# Trinamic.net
KiCad netlist of a schematic drawn in Altium Designer
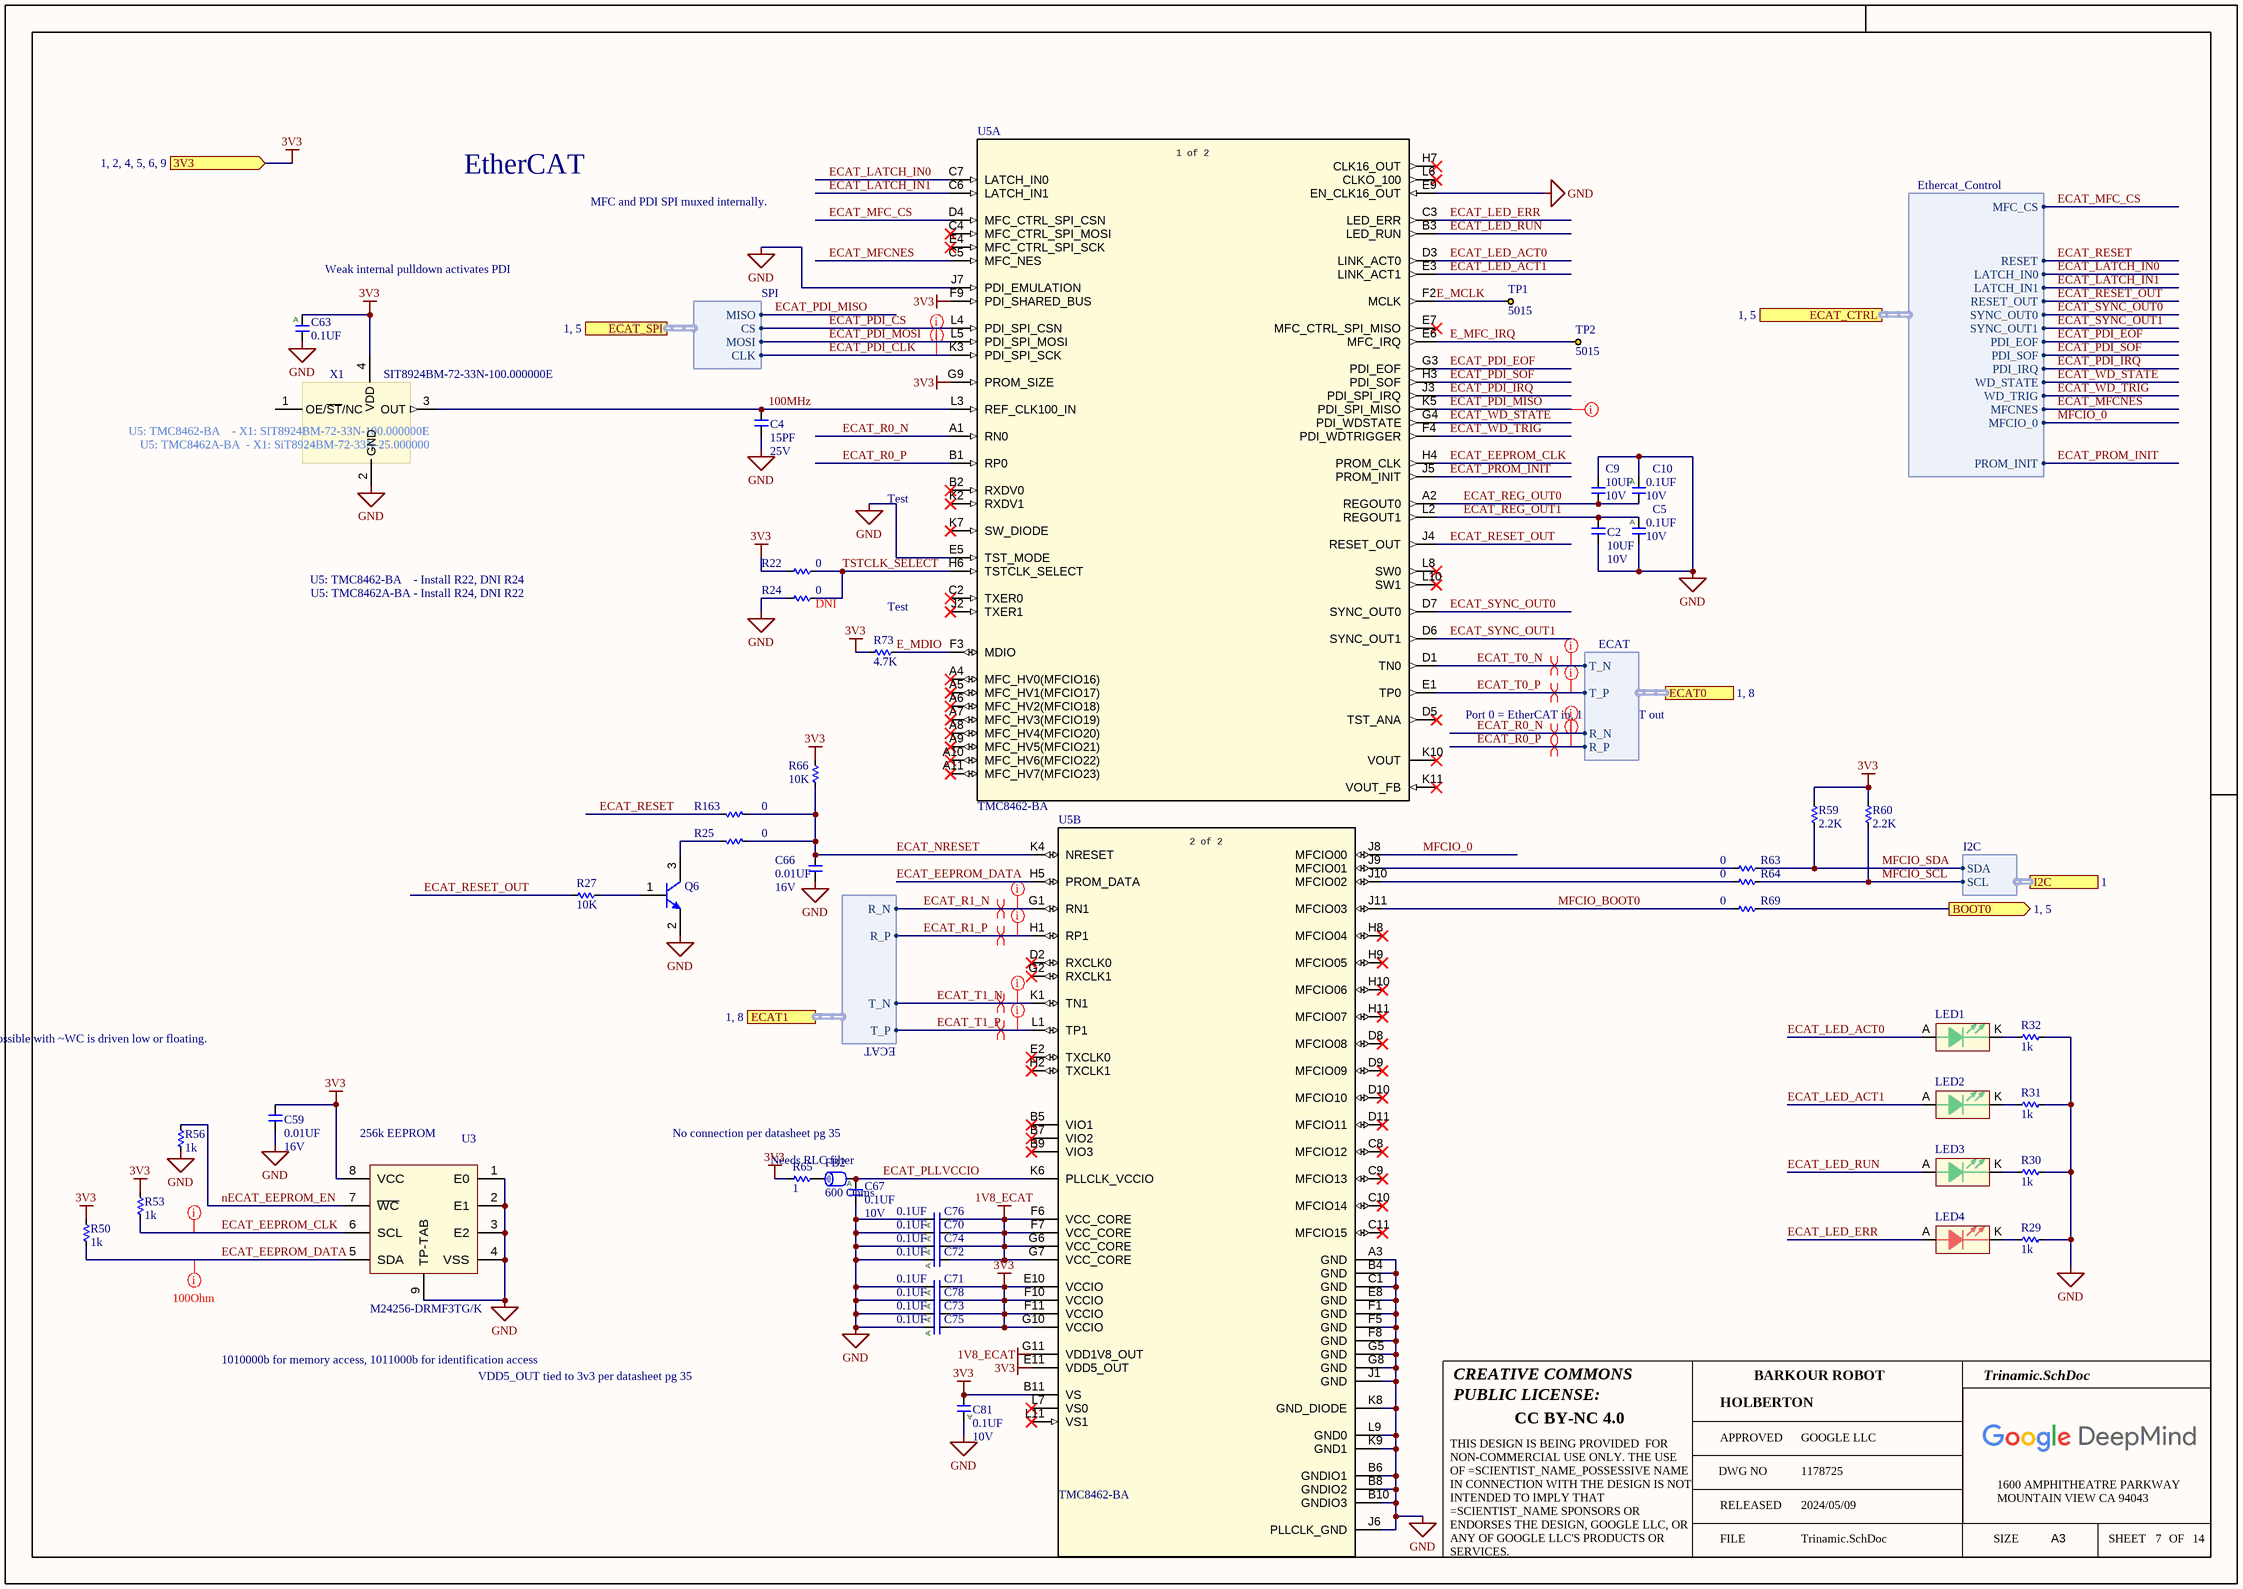
[diagram p0: Trinamic.SchDoc]

(export (version "E")
  (design (tool "Eeschema 10.0.6"))
  (components
    (comp (ref "C2")
      (value "10UF")
      (footprint "C0402")
      (description "CAP, CER, X5R, 10uF, 10V, 20%, 0402, 0.7mm T")
      (fields
        (field (name "MFG") "SAMSUNG")
        (field (name "VOLTAGE") "10V")
        (field (name "Comment") "__Template_Cap")
      )
      (libsource (lib "AltiumReleaseLibDB") (part "__Template_Cap"))
    )
    (comp (ref "C4")
      (value "15PF")
      (footprint "C0201")
      (description "CAP, CER, NP0, 15pF, 25V, 5%, 0201, 0.9mm T")
      (fields
        (field (name "MFG") "TDK")
        (field (name "VOLTAGE") "25V")
        (field (name "Comment") "__Template_Cap")
      )
      (libsource (lib "AltiumReleaseLibDB") (part "__Template_Cap"))
    )
    (comp (ref "C5")
      (value "0.1UF")
      (footprint "C0201")
      (description "CAP, CER, X6S, 0.1uF, 10V, 10%, 0201, AUTOGRADE")
      (fields
        (field (name "MFG") "MURATA")
        (field (name "VOLTAGE") "10V")
        (field (name "Comment") "__Template_Cap_Auto")
      )
      (libsource (lib "AltiumReleaseLibDB") (part "__Template_Cap_Auto"))
    )
    (comp (ref "C9")
      (value "10UF")
      (footprint "C0402")
      (description "CAP, CER, X5R, 10uF, 10V, 20%, 0402, 0.7mm T")
      (fields
        (field (name "MFG") "SAMSUNG")
        (field (name "VOLTAGE") "10V")
        (field (name "Comment") "__Template_Cap")
      )
      (libsource (lib "AltiumReleaseLibDB") (part "__Template_Cap"))
    )
    (comp (ref "C10")
      (value "0.1UF")
      (footprint "C0201")
      (description "CAP, CER, X6S, 0.1uF, 10V, 10%, 0201, AUTOGRADE")
      (fields
        (field (name "MFG") "MURATA")
        (field (name "VOLTAGE") "10V")
        (field (name "Comment") "__Template_Cap_Auto")
      )
      (libsource (lib "AltiumReleaseLibDB") (part "__Template_Cap_Auto"))
    )
    (comp (ref "C59")
      (value "0.01UF")
      (footprint "C0201")
      (description "CAP, CER, X5R, 0.01uF, 16V, 10%, 0201, 0.33mm T")
      (fields
        (field (name "MFG") "MURATA")
        (field (name "VOLTAGE") "16V")
        (field (name "Comment") "__Template_Cap")
      )
      (libsource (lib "AltiumReleaseLibDB") (part "__Template_Cap"))
    )
    (comp (ref "C63")
      (value "0.1UF")
      (footprint "C0201")
      (description "CAP, CER, X6S, 0.1uF, 10V, 10%, 0201, AUTOGRADE")
      (fields (field (name "MFG") "MURATA") (field (name "VOLTAGE") "10V"))
      (libsource (lib "AltiumReleaseLibDB") (part "__Template_Cap_Auto"))
    )
    (comp (ref "C66")
      (value "0.01UF")
      (footprint "C0201")
      (description "CAP, CER, X5R, 0.01uF, 16V, 10%, 0201, 0.33mm T")
      (fields
        (field (name "MFG") "MURATA")
        (field (name "VOLTAGE") "16V")
        (field (name "Comment") "__Template_Cap")
      )
      (libsource (lib "AltiumReleaseLibDB") (part "__Template_Cap"))
    )
    (comp (ref "C67")
      (value "0.1UF")
      (footprint "C0201")
      (description "CAP, CER, X6S, 0.1uF, 10V, 10%, 0201, AUTOGRADE")
      (fields
        (field (name "MFG") "MURATA")
        (field (name "VOLTAGE") "10V")
        (field (name "Comment") "__Template_Cap_Auto")
      )
      (libsource (lib "AltiumReleaseLibDB") (part "__Template_Cap_Auto"))
    )
    (comp (ref "C70")
      (value "0.1UF")
      (footprint "C0201")
      (description "CAP, CER, X6S, 0.1uF, 10V, 10%, 0201, AUTOGRADE")
      (fields (field (name "MFG") "MURATA") (field (name "VOLTAGE") "10V"))
      (libsource (lib "AltiumReleaseLibDB") (part "__Template_Cap_Auto"))
    )
    (comp (ref "C71")
      (value "0.1UF")
      (footprint "C0201")
      (description "CAP, CER, X6S, 0.1uF, 10V, 10%, 0201, AUTOGRADE")
      (fields (field (name "MFG") "MURATA") (field (name "VOLTAGE") "10V"))
      (libsource (lib "AltiumReleaseLibDB") (part "__Template_Cap_Auto"))
    )
    (comp (ref "C72")
      (value "0.1UF")
      (footprint "C0201")
      (description "CAP, CER, X6S, 0.1uF, 10V, 10%, 0201, AUTOGRADE")
      (fields (field (name "MFG") "MURATA") (field (name "VOLTAGE") "10V"))
      (libsource (lib "AltiumReleaseLibDB") (part "__Template_Cap_Auto"))
    )
    (comp (ref "C73")
      (value "0.1UF")
      (footprint "C0201")
      (description "CAP, CER, X6S, 0.1uF, 10V, 10%, 0201, AUTOGRADE")
      (fields (field (name "MFG") "MURATA") (field (name "VOLTAGE") "10V"))
      (libsource (lib "AltiumReleaseLibDB") (part "__Template_Cap_Auto"))
    )
    (comp (ref "C74")
      (value "0.1UF")
      (footprint "C0201")
      (description "CAP, CER, X6S, 0.1uF, 10V, 10%, 0201, AUTOGRADE")
      (fields (field (name "MFG") "MURATA") (field (name "VOLTAGE") "10V"))
      (libsource (lib "AltiumReleaseLibDB") (part "__Template_Cap_Auto"))
    )
    (comp (ref "C75")
      (value "0.1UF")
      (footprint "C0201")
      (description "CAP, CER, X6S, 0.1uF, 10V, 10%, 0201, AUTOGRADE")
      (fields (field (name "MFG") "MURATA") (field (name "VOLTAGE") "10V"))
      (libsource (lib "AltiumReleaseLibDB") (part "__Template_Cap_Auto"))
    )
    (comp (ref "C76")
      (value "0.1UF")
      (footprint "C0201")
      (description "CAP, CER, X6S, 0.1uF, 10V, 10%, 0201, AUTOGRADE")
      (fields (field (name "MFG") "MURATA") (field (name "VOLTAGE") "10V"))
      (libsource (lib "AltiumReleaseLibDB") (part "__Template_Cap_Auto"))
    )
    (comp (ref "C78")
      (value "0.1UF")
      (footprint "C0201")
      (description "CAP, CER, X6S, 0.1uF, 10V, 10%, 0201, AUTOGRADE")
      (fields (field (name "MFG") "MURATA") (field (name "VOLTAGE") "10V"))
      (libsource (lib "AltiumReleaseLibDB") (part "__Template_Cap_Auto"))
    )
    (comp (ref "C81")
      (value "0.1UF")
      (footprint "C0201")
      (description "CAP, CER, X6S, 0.1uF, 10V, 10%, 0201, AUTOGRADE")
      (fields
        (field (name "MFG") "MURATA")
        (field (name "VOLTAGE") "10V")
        (field (name "Comment") "__Template_Cap_Auto")
      )
      (libsource (lib "AltiumReleaseLibDB") (part "__Template_Cap_Auto"))
    )
    (comp (ref "FB2")
      (value "600 Ohms")
      (footprint "L0201_H0.33MM")
      (description "FERRITE, BEAD, 600OHMS @100MHZ, 25%, 250mA, 900 mOHM DCR, 0201")
      (fields
        (field (name "MFG") "Murata Electronics North America")
        (field (name "Comment") "__Template_Ferrite_Bead")
      )
      (libsource (lib "AltiumReleaseLibDB") (part "__Template_Ferrite_Bead"))
    )
    (comp (ref "LED1")
      (value "__Template_LED_GREEN_AK")
      (footprint "LED_APHHS1005LCGCK")
      (description "LED, GREEN, 574nm, 2mA, CLEAR, 0402")
      (fields (field (name "MFG") "Kingbright"))
      (libsource (lib "AltiumReleaseLibDB") (part "__Template_LED_GREEN_AK"))
    )
    (comp (ref "LED2")
      (value "__Template_LED_GREEN_AK")
      (footprint "LED_APHHS1005LCGCK")
      (description "LED, GREEN, 574nm, 2mA, CLEAR, 0402")
      (fields (field (name "MFG") "Kingbright"))
      (libsource (lib "AltiumReleaseLibDB") (part "__Template_LED_GREEN_AK"))
    )
    (comp (ref "LED3")
      (value "__Template_LED_GREEN_AK")
      (footprint "LED_APHHS1005LCGCK")
      (description "LED, GREEN, 574nm, 2mA, CLEAR, 0402")
      (fields (field (name "MFG") "Kingbright"))
      (libsource (lib "AltiumReleaseLibDB") (part "__Template_LED_GREEN_AK"))
    )
    (comp (ref "LED4")
      (value "__Template_LED_RED_AK")
      (footprint "LED_APHHS1005LCGCK")
      (description "LED, RED, 640NM, 2mA, CLEAR, 0402")
      (fields (field (name "MFG") "Kingbright"))
      (libsource (lib "AltiumReleaseLibDB") (part "__Template_LED_RED_AK"))
    )
    (comp (ref "Q6")
      (value "Bipolar NPN 3 Pins Transistor Gummel-Poon Model")
      (footprint "SOT23-3")
      (description "TRANS NPN 40V 0.2A SOT23-3")
      (fields (field (name "MFG") "NTE Electronics, Inc"))
      (libsource (lib "Holberton_V1") (part "BJT NPN_GP"))
    )
    (comp (ref "R22")
      (value "0")
      (footprint "R0402")
      (description "RES, 0, JUMPER, 1/16W, 0402")
      (fields (field (name "MFG") "YAGEO"))
      (libsource (lib "AltiumReleaseLibDB") (part "__Template_Resistor"))
    )
    (comp (ref "R24")
      (value "0")
      (footprint "R0402")
      (description "RES, 0, JUMPER, 1/16W, 0402")
      (fields (field (name "MFG") "YAGEO") (field (name "DNI") "DNI"))
      (libsource (lib "AltiumReleaseLibDB") (part "__Template_Resistor"))
    )
    (comp (ref "R25")
      (value "0")
      (footprint "R0402")
      (description "RES, 0, JUMPER, 1/16W, 0402")
      (fields (field (name "MFG") "YAGEO"))
      (libsource (lib "AltiumReleaseLibDB") (part "__Template_Resistor"))
    )
    (comp (ref "R27")
      (value "10K")
      (footprint "R0201")
      (description "RES, 10K, 1%, 1/20W, 0201, AUTOGRADE")
      (fields (field (name "MFG") "PANASONIC") (field (name "Comment") "__Template_Resistor"))
      (libsource (lib "AltiumReleaseLibDB") (part "__Template_Resistor"))
    )
    (comp (ref "R29")
      (value "1k")
      (footprint "R0201")
      (description "RES, 1K, 1%, 1/20W, 0201, AUTOGRADE")
      (fields (field (name "MFG") "Bourns Inc.") (field (name "Comment") "__Template_Resistor"))
      (libsource (lib "AltiumReleaseLibDB") (part "__Template_Resistor"))
    )
    (comp (ref "R30")
      (value "1k")
      (footprint "R0201")
      (description "RES, 1K, 1%, 1/20W, 0201, AUTOGRADE")
      (fields (field (name "MFG") "Bourns Inc.") (field (name "Comment") "__Template_Resistor"))
      (libsource (lib "AltiumReleaseLibDB") (part "__Template_Resistor"))
    )
    (comp (ref "R31")
      (value "1k")
      (footprint "R0201")
      (description "RES, 1K, 1%, 1/20W, 0201, AUTOGRADE")
      (fields (field (name "MFG") "Bourns Inc.") (field (name "Comment") "__Template_Resistor"))
      (libsource (lib "AltiumReleaseLibDB") (part "__Template_Resistor"))
    )
    (comp (ref "R32")
      (value "1k")
      (footprint "R0201")
      (description "RES, 1K, 1%, 1/20W, 0201, AUTOGRADE")
      (fields (field (name "MFG") "Bourns Inc.") (field (name "Comment") "__Template_Resistor"))
      (libsource (lib "AltiumReleaseLibDB") (part "__Template_Resistor"))
    )
    (comp (ref "R50")
      (value "1k")
      (footprint "R0201")
      (description "RES, 1K, 1%, 1/20W, 0201, AUTOGRADE")
      (fields (field (name "MFG") "Bourns Inc.") (field (name "Comment") "__Template_Resistor"))
      (libsource (lib "AltiumReleaseLibDB") (part "__Template_Resistor"))
    )
    (comp (ref "R53")
      (value "1k")
      (footprint "R0201")
      (description "RES, 1K, 1%, 1/20W, 0201, AUTOGRADE")
      (fields (field (name "MFG") "Bourns Inc.") (field (name "Comment") "__Template_Resistor"))
      (libsource (lib "AltiumReleaseLibDB") (part "__Template_Resistor"))
    )
    (comp (ref "R56")
      (value "1k")
      (footprint "R0201")
      (description "RES, 1K, 1%, 1/20W, 0201, AUTOGRADE")
      (fields (field (name "MFG") "Bourns Inc.") (field (name "Comment") "__Template_Resistor"))
      (libsource (lib "AltiumReleaseLibDB") (part "__Template_Resistor"))
    )
    (comp (ref "R59")
      (value "2.2K")
      (footprint "R0201")
      (description "Resistor, 2.20K Ohms, 0201, 0.05W, ±1%")
      (fields (field (name "MFG") "PANASONIC"))
      (libsource (lib "AltiumReleaseLibDB") (part "__Template_Resistor"))
    )
    (comp (ref "R60")
      (value "2.2K")
      (footprint "R0201")
      (description "Resistor, 2.20K Ohms, 0201, 0.05W, ±1%")
      (fields (field (name "MFG") "PANASONIC"))
      (libsource (lib "AltiumReleaseLibDB") (part "__Template_Resistor"))
    )
    (comp (ref "R63")
      (value "0")
      (footprint "R0402")
      (description "RES, 0, JUMPER, 1/16W, 0402")
      (fields (field (name "MFG") "YAGEO"))
      (libsource (lib "AltiumReleaseLibDB") (part "__Template_Resistor"))
    )
    (comp (ref "R64")
      (value "0")
      (footprint "R0402")
      (description "RES, 0, JUMPER, 1/16W, 0402")
      (fields (field (name "MFG") "YAGEO"))
      (libsource (lib "AltiumReleaseLibDB") (part "__Template_Resistor"))
    )
    (comp (ref "R65")
      (value "1")
      (footprint "R0201")
      (description "RES, 1.0, 5%, 1/20W, 0201")
      (fields (field (name "MFG") "PANASONIC"))
      (libsource (lib "AltiumReleaseLibDB") (part "__Template_Resistor"))
    )
    (comp (ref "R66")
      (value "10K")
      (footprint "R0201")
      (description "RES, 10K, 1%, 1/20W, 0201, AUTOGRADE")
      (fields (field (name "MFG") "PANASONIC") (field (name "Comment") "__Template_Resistor"))
      (libsource (lib "AltiumReleaseLibDB") (part "__Template_Resistor"))
    )
    (comp (ref "R69")
      (value "0")
      (footprint "R0402")
      (description "RES, 0, JUMPER, 1/16W, 0402")
      (fields (field (name "MFG") "YAGEO"))
      (libsource (lib "AltiumReleaseLibDB") (part "__Template_Resistor"))
    )
    (comp (ref "R73")
      (value "4.7K")
      (footprint "R0201")
      (description "RES, 4.7K, 1%, 1/20W, 0201, AUTOGRADE")
      (fields
        (field (name "MFG") "Panasonic Electronic Components")
        (field (name "Comment") "__Template_Resistor")
      )
      (libsource (lib "AltiumReleaseLibDB") (part "__Template_Resistor"))
    )
    (comp (ref "R163")
      (value "0")
      (footprint "R0402")
      (description "RES, 0, JUMPER, 1/16W, 0402")
      (fields (field (name "MFG") "YAGEO"))
      (libsource (lib "AltiumReleaseLibDB") (part "__Template_Resistor"))
    )
    (comp (ref "TP1")
      (value "TP_KEYSTONE_5015")
      (footprint "TP_KEYSTONE_5015")
      (description "PC TEST POINT MINIATURE SMT")
      (fields (field (name "MFG") "Keystone Electronics") (field (name "MFG P/N") "5015"))
      (libsource (lib "AltiumReleaseLibDB") (part "TEST_KEYSTONE5015_NOSILK"))
    )
    (comp (ref "TP2")
      (value "TP_KEYSTONE_5015")
      (footprint "TP_KEYSTONE_5015")
      (description "PC TEST POINT MINIATURE SMT")
      (fields (field (name "MFG") "Keystone Electronics") (field (name "MFG P/N") "5015"))
      (libsource (lib "AltiumReleaseLibDB") (part "TEST_KEYSTONE5015_NOSILK"))
    )
    (comp (ref "U3")
      (value "EEPROM_M24256-DRMF3TG/K")
      (footprint "8WFDFN300X200X80-8-TP")
      (description "IC, MEMORY, M24256, EEPROM, 256Kb, I2C, 1MHz, MLP-8, AUTOGRADE")
      (fields (field (name "MFG") "STMicroelectronics") (field (name "MFG P/N") "M24256-DRMF3TG/K"))
      (libsource (lib "AltiumReleaseLibDB") (part "EEPROM_M24256-DRMF3TG/K"))
    )
    (comp (ref "U5")
      (value "PROCESSOR_TRINAMIC_TMC8462-BA")
      (footprint "BGA121C75P11X11_900X900X145")
      (description "IC, CONTROLLER, TMC8462, ETHERNET, 100Mb, SPI, PWM O/P, 100mA, BGA-121")
      (fields (field (name "MFG") "Trinamic Motion Control GmbH") (field (name "MFG P/N") "TMC8462-BA"))
      (libsource (lib "AltiumReleaseLibDB") (part "PROCESSOR_TRINAMIC_TMC8462-BA"))
    )
    (comp (ref "X1")
      (value "XTAL_SIT8924BM-72-33N-100.000000")
      (footprint "XTAL_SIT8924BM-72-33N-100.000000")
      (description "OSC, MEMS, XO, 100MHZ, +/-25PPM STAB, LVCMOS, 3.3V, SMD-4, AUTOGRADE")
      (fields (field (name "MFG") "SiTIME") (field (name "MFG P/N") "SIT8924BM-72-33N-100.000000E"))
      (libsource (lib "AltiumReleaseLibDB") (part "XTAL_SIT8924BM-72-33N-100.000000"))
    )
  )
  (nets
    (net (code "5") (name "/100MHz") (class "Default")
      (node (ref "C4") (pin "1") (pintype "passive"))
      (node (ref "U5") (pin "L3") (pinfunction "REF_CLK100_IN_L3") (pintype "input"))
      (node (ref "X1") (pin "3") (pinfunction "OUT_3") (pintype "output"))
    )
    (net (code "6") (name "/BOOT0") (class "Default") (node (ref "R69") (pin "2") (pintype "passive")))
    (net (code "7") (name "/ECAT_EEPROM_CLK") (class "Default")
      (node (ref "R53") (pin "1") (pintype "passive"))
      (node (ref "U3") (pin "6") (pinfunction "SCL_6") (pintype "passive"))
      (node (ref "U5") (pin "H4") (pinfunction "PROM_CLK_H4") (pintype "output"))
    )
    (net (code "8") (name "/ECAT_EEPROM_DATA") (class "Default")
      (node (ref "R50") (pin "1") (pintype "passive"))
      (node (ref "U3") (pin "5") (pinfunction "SDA_5") (pintype "passive"))
      (node (ref "U5") (pin "H5") (pinfunction "PROM_DATA_H5") (pintype "bidirectional"))
    )
    (net (code "9") (name "/ECAT_LATCH_IN0") (class "Default")
      (node (ref "U5") (pin "C7") (pinfunction "LATCH_IN0_C7") (pintype "input"))
    )
    (net (code "10") (name "/ECAT_LATCH_IN1") (class "Default")
      (node (ref "U5") (pin "C6") (pinfunction "LATCH_IN1_C6") (pintype "input"))
    )
    (net (code "11") (name "/ECAT_LED_ACT0") (class "Default")
      (node (ref "LED1") (pin "A") (pinfunction "A_A") (pintype "passive"))
      (node (ref "U5") (pin "D3") (pinfunction "LINK_ACT0_D3") (pintype "output"))
    )
    (net (code "12") (name "/ECAT_LED_ACT1") (class "Default")
      (node (ref "LED2") (pin "A") (pinfunction "A_A") (pintype "passive"))
      (node (ref "U5") (pin "E3") (pinfunction "LINK_ACT1_E3") (pintype "output"))
    )
    (net (code "13") (name "/ECAT_LED_ERR") (class "Default")
      (node (ref "LED4") (pin "A") (pinfunction "A_A") (pintype "passive"))
      (node (ref "U5") (pin "C3") (pinfunction "LED_ERR_C3") (pintype "output"))
    )
    (net (code "14") (name "/ECAT_LED_RUN") (class "Default")
      (node (ref "LED3") (pin "A") (pinfunction "A_A") (pintype "passive"))
      (node (ref "U5") (pin "B3") (pinfunction "LED_RUN_B3") (pintype "output"))
    )
    (net (code "15") (name "/ECAT_MFCNES") (class "Default")
      (node (ref "U5") (pin "C5") (pinfunction "MFC_NES_C5") (pintype "input"))
    )
    (net (code "16") (name "/ECAT_MFC_CS") (class "Default")
      (node (ref "U5") (pin "D4") (pinfunction "MFC_CTRL_SPI_CSN_D4") (pintype "input"))
    )
    (net (code "17") (name "/ECAT_NRESET") (class "Default")
      (node (ref "C66") (pin "1") (pintype "passive"))
      (node (ref "R163") (pin "1") (pintype "passive"))
      (node (ref "R25") (pin "1") (pintype "passive"))
      (node (ref "R66") (pin "1") (pintype "passive"))
      (node (ref "U5") (pin "K4") (pinfunction "NRESET_K4") (pintype "bidirectional"))
    )
    (net (code "18") (name "/ECAT_PDI_CLK") (class "Default")
      (node (ref "U5") (pin "K3") (pinfunction "PDI_SPI_SCK_K3") (pintype "input"))
    )
    (net (code "19") (name "/ECAT_PDI_CS") (class "Default")
      (node (ref "U5") (pin "L4") (pinfunction "PDI_SPI_CSN_L4") (pintype "input"))
    )
    (net (code "20") (name "/ECAT_PDI_EOF") (class "Default")
      (node (ref "U5") (pin "G3") (pinfunction "PDI_EOF_G3") (pintype "output"))
    )
    (net (code "21") (name "/ECAT_PDI_IRQ") (class "Default")
      (node (ref "U5") (pin "J3") (pinfunction "PDI_SPI_IRQ_J3") (pintype "output"))
    )
    (net (code "22") (name "/ECAT_PDI_MISO") (class "Default")
      (node (ref "U5") (pin "K5") (pinfunction "PDI_SPI_MISO_K5") (pintype "output"))
    )
    (net (code "23") (name "/ECAT_PDI_MOSI") (class "Default")
      (node (ref "U5") (pin "L5") (pinfunction "PDI_SPI_MOSI_L5") (pintype "input"))
    )
    (net (code "24") (name "/ECAT_PDI_SOF") (class "Default")
      (node (ref "U5") (pin "H3") (pinfunction "PDI_SOF_H3") (pintype "output"))
    )
    (net (code "25") (name "/ECAT_PLLVCCIO") (class "Default")
      (node (ref "C67") (pin "1") (pintype "passive"))
      (node (ref "FB2") (pin "2") (pinfunction "2_2") (pintype "passive"))
      (node (ref "U5") (pin "K6") (pinfunction "PLLCLK_VCCIO_K6") (pintype "power_in"))
    )
    (net (code "26") (name "/ECAT_PROM_INIT") (class "Default")
      (node (ref "U5") (pin "J5") (pinfunction "PROM_INIT_J5") (pintype "output"))
    )
    (net (code "27") (name "/ECAT_R0_N") (class "Default")
      (node (ref "U5") (pin "A1") (pinfunction "RN0_A1") (pintype "input"))
    )
    (net (code "28") (name "/ECAT_R0_P") (class "Default")
      (node (ref "U5") (pin "B1") (pinfunction "RP0_B1") (pintype "input"))
    )
    (net (code "29") (name "/ECAT_R1_N") (class "Default")
      (node (ref "U5") (pin "G1") (pinfunction "RN1_G1") (pintype "bidirectional"))
    )
    (net (code "30") (name "/ECAT_R1_P") (class "Default")
      (node (ref "U5") (pin "H1") (pinfunction "RP1_H1") (pintype "bidirectional"))
    )
    (net (code "31") (name "/ECAT_REG_OUT0") (class "Default")
      (node (ref "C10") (pin "2") (pintype "passive"))
      (node (ref "C9") (pin "2") (pintype "passive"))
      (node (ref "U5") (pin "A2") (pinfunction "REGOUT0_A2") (pintype "output"))
    )
    (net (code "32") (name "/ECAT_REG_OUT1") (class "Default")
      (node (ref "C2") (pin "1") (pintype "passive"))
      (node (ref "C5") (pin "1") (pintype "passive"))
      (node (ref "U5") (pin "L2") (pinfunction "REGOUT1_L2") (pintype "output"))
    )
    (net (code "33") (name "/ECAT_RESET") (class "Default") (node (ref "R163") (pin "2") (pintype "passive")))
    (net (code "34") (name "/ECAT_RESET_OUT") (class "Default")
      (node (ref "R27") (pin "2") (pintype "passive"))
      (node (ref "U5") (pin "J4") (pinfunction "RESET_OUT_J4") (pintype "output"))
    )
    (net (code "35") (name "/ECAT_SYNC_OUT0") (class "Default")
      (node (ref "U5") (pin "D7") (pinfunction "SYNC_OUT0_D7") (pintype "output"))
    )
    (net (code "36") (name "/ECAT_SYNC_OUT1") (class "Default")
      (node (ref "U5") (pin "D6") (pinfunction "SYNC_OUT1_D6") (pintype "output"))
    )
    (net (code "37") (name "/ECAT_T0_N") (class "Default")
      (node (ref "U5") (pin "D1") (pinfunction "TN0_D1") (pintype "output"))
    )
    (net (code "38") (name "/ECAT_T0_P") (class "Default")
      (node (ref "U5") (pin "E1") (pinfunction "TP0_E1") (pintype "output"))
    )
    (net (code "39") (name "/ECAT_T1_N") (class "Default")
      (node (ref "U5") (pin "K1") (pinfunction "TN1_K1") (pintype "bidirectional"))
    )
    (net (code "40") (name "/ECAT_T1_P") (class "Default")
      (node (ref "U5") (pin "L1") (pinfunction "TP1_L1") (pintype "bidirectional"))
    )
    (net (code "41") (name "/ECAT_WD_STATE") (class "Default")
      (node (ref "U5") (pin "G4") (pinfunction "PDI_WDSTATE_G4") (pintype "output"))
    )
    (net (code "42") (name "/ECAT_WD_TRIG") (class "Default")
      (node (ref "U5") (pin "F4") (pinfunction "PDI_WDTRIGGER_F4") (pintype "output"))
    )
    (net (code "43") (name "/E_MCLK") (class "Default")
      (node (ref "TP1") (pin "1") (pintype "passive"))
      (node (ref "U5") (pin "F2") (pinfunction "MCLK_F2") (pintype "output"))
    )
    (net (code "44") (name "/E_MDIO") (class "Default")
      (node (ref "R73") (pin "1") (pintype "passive"))
      (node (ref "U5") (pin "F3") (pinfunction "MDIO_F3") (pintype "bidirectional"))
    )
    (net (code "45") (name "/E_MFC_IRQ") (class "Default")
      (node (ref "TP2") (pin "1") (pintype "passive"))
      (node (ref "U5") (pin "E6") (pinfunction "MFC_IRQ_E6") (pintype "output"))
    )
    (net (code "46") (name "/MFCIO_0") (class "Default")
      (node (ref "U5") (pin "J8") (pinfunction "MFCIO00_J8") (pintype "bidirectional"))
    )
    (net (code "47") (name "/MFCIO_BOOT0") (class "Default")
      (node (ref "R69") (pin "1") (pintype "passive"))
      (node (ref "U5") (pin "J11") (pinfunction "MFCIO03_J11") (pintype "bidirectional"))
    )
    (net (code "48") (name "/MFCIO_SCL") (class "Default")
      (node (ref "R60") (pin "1") (pintype "passive"))
      (node (ref "R64") (pin "2") (pintype "passive"))
    )
    (net (code "49") (name "/MFCIO_SDA") (class "Default")
      (node (ref "R59") (pin "1") (pintype "passive"))
      (node (ref "R63") (pin "2") (pintype "passive"))
    )
    (net (code "50") (name "/TSTCLK_SELECT") (class "Default")
      (node (ref "R22") (pin "2") (pintype "passive"))
      (node (ref "R24") (pin "2") (pintype "passive"))
      (node (ref "U5") (pin "H6") (pinfunction "TSTCLK_SELECT_H6") (pintype "input"))
    )
    (net (code "51") (name "/nECAT_EEPROM_EN") (class "Default")
      (node (ref "R56") (pin "2") (pintype "passive"))
      (node (ref "U3") (pin "7") (pinfunction "~{WC}_7") (pintype "passive"))
    )
    (net (code "56") (name "1V8_ECAT") (class "Default")
      (node (ref "C70") (pin "2") (pintype "passive"))
      (node (ref "C72") (pin "2") (pintype "passive"))
      (node (ref "C74") (pin "2") (pintype "passive"))
      (node (ref "C76") (pin "2") (pintype "passive"))
      (node (ref "U5") (pin "F6") (pinfunction "VCC_CORE_F6") (pintype "power_in"))
      (node (ref "U5") (pin "F7") (pinfunction "VCC_CORE_F7") (pintype "power_in"))
      (node (ref "U5") (pin "G11") (pinfunction "VDD1V8_OUT_G11") (pintype "power_in"))
      (node (ref "U5") (pin "G6") (pinfunction "VCC_CORE_G6") (pintype "power_in"))
      (node (ref "U5") (pin "G7") (pinfunction "VCC_CORE_G7") (pintype "power_in"))
    )
    (net (code "57") (name "3V3") (class "Default")
      (node (ref "C59") (pin "1") (pintype "passive"))
      (node (ref "C63") (pin "1") (pintype "passive"))
      (node (ref "C71") (pin "2") (pintype "passive"))
      (node (ref "C73") (pin "2") (pintype "passive"))
      (node (ref "C75") (pin "2") (pintype "passive"))
      (node (ref "C78") (pin "2") (pintype "passive"))
      (node (ref "C81") (pin "2") (pintype "passive"))
      (node (ref "R22") (pin "1") (pintype "passive"))
      (node (ref "R50") (pin "2") (pintype "passive"))
      (node (ref "R53") (pin "2") (pintype "passive"))
      (node (ref "R59") (pin "2") (pintype "passive"))
      (node (ref "R60") (pin "2") (pintype "passive"))
      (node (ref "R65") (pin "1") (pintype "passive"))
      (node (ref "R66") (pin "2") (pintype "passive"))
      (node (ref "R73") (pin "2") (pintype "passive"))
      (node (ref "U3") (pin "8") (pinfunction "VCC_8") (pintype "passive"))
      (node (ref "U5") (pin "B11") (pinfunction "VS_B11") (pintype "power_in"))
      (node (ref "U5") (pin "E10") (pinfunction "VCCIO_E10") (pintype "power_in"))
      (node (ref "U5") (pin "E11") (pinfunction "VDD5_OUT_E11") (pintype "power_in"))
      (node (ref "U5") (pin "F10") (pinfunction "VCCIO_F10") (pintype "power_in"))
      (node (ref "U5") (pin "F11") (pinfunction "VCCIO_F11") (pintype "power_in"))
      (node (ref "U5") (pin "F9") (pinfunction "PDI_SHARED_BUS_F9") (pintype "input"))
      (node (ref "U5") (pin "G10") (pinfunction "VCCIO_G10") (pintype "power_in"))
      (node (ref "U5") (pin "G9") (pinfunction "PROM_SIZE_G9") (pintype "input"))
      (node (ref "X1") (pin "4") (pinfunction "VDD_4") (pintype "power_in"))
    )
    (net (code "58") (name "GND") (class "Default")
      (node (ref "C10") (pin "1") (pintype "passive"))
      (node (ref "C2") (pin "2") (pintype "passive"))
      (node (ref "C4") (pin "2") (pintype "passive"))
      (node (ref "C5") (pin "2") (pintype "passive"))
      (node (ref "C59") (pin "2") (pintype "passive"))
      (node (ref "C63") (pin "2") (pintype "passive"))
      (node (ref "C66") (pin "2") (pintype "passive"))
      (node (ref "C67") (pin "2") (pintype "passive"))
      (node (ref "C70") (pin "1") (pintype "passive"))
      (node (ref "C71") (pin "1") (pintype "passive"))
      (node (ref "C72") (pin "1") (pintype "passive"))
      (node (ref "C73") (pin "1") (pintype "passive"))
      (node (ref "C74") (pin "1") (pintype "passive"))
      (node (ref "C75") (pin "1") (pintype "passive"))
      (node (ref "C76") (pin "1") (pintype "passive"))
      (node (ref "C78") (pin "1") (pintype "passive"))
      (node (ref "C81") (pin "1") (pintype "passive"))
      (node (ref "C9") (pin "1") (pintype "passive"))
      (node (ref "Q6") (pin "2") (pinfunction "E_2") (pintype "passive"))
      (node (ref "R24") (pin "1") (pintype "passive"))
      (node (ref "R29") (pin "1") (pintype "passive"))
      (node (ref "R30") (pin "1") (pintype "passive"))
      (node (ref "R31") (pin "1") (pintype "passive"))
      (node (ref "R32") (pin "1") (pintype "passive"))
      (node (ref "R56") (pin "1") (pintype "passive"))
      (node (ref "U3") (pin "1") (pinfunction "E0_1") (pintype "passive"))
      (node (ref "U3") (pin "2") (pinfunction "E1_2") (pintype "passive"))
      (node (ref "U3") (pin "3") (pinfunction "E2_3") (pintype "passive"))
      (node (ref "U3") (pin "4") (pinfunction "VSS_4") (pintype "passive"))
      (node (ref "U3") (pin "9") (pinfunction "TP-TAB_9") (pintype "power_in"))
      (node (ref "U5") (pin "A3") (pinfunction "GND_A3") (pintype "power_in"))
      (node (ref "U5") (pin "B10") (pinfunction "GNDIO3_B10") (pintype "power_in"))
      (node (ref "U5") (pin "B4") (pinfunction "GND_B4") (pintype "power_in"))
      (node (ref "U5") (pin "B6") (pinfunction "GNDIO1_B6") (pintype "power_in"))
      (node (ref "U5") (pin "B8") (pinfunction "GNDIO2_B8") (pintype "power_in"))
      (node (ref "U5") (pin "C1") (pinfunction "GND_C1") (pintype "power_in"))
      (node (ref "U5") (pin "E5") (pinfunction "TST_MODE_E5") (pintype "input"))
      (node (ref "U5") (pin "E8") (pinfunction "GND_E8") (pintype "power_in"))
      (node (ref "U5") (pin "E9") (pinfunction "EN_CLK16_OUT_E9") (pintype "input"))
      (node (ref "U5") (pin "F1") (pinfunction "GND_F1") (pintype "power_in"))
      (node (ref "U5") (pin "F5") (pinfunction "GND_F5") (pintype "power_in"))
      (node (ref "U5") (pin "F8") (pinfunction "GND_F8") (pintype "power_in"))
      (node (ref "U5") (pin "G5") (pinfunction "GND_G5") (pintype "power_in"))
      (node (ref "U5") (pin "G8") (pinfunction "GND_G8") (pintype "power_in"))
      (node (ref "U5") (pin "J1") (pinfunction "GND_J1") (pintype "power_in"))
      (node (ref "U5") (pin "J6") (pinfunction "PLLCLK_GND_J6") (pintype "power_in"))
      (node (ref "U5") (pin "J7") (pinfunction "PDI_EMULATION_J7") (pintype "input"))
      (node (ref "U5") (pin "K8") (pinfunction "GND_DIODE_K8") (pintype "power_in"))
      (node (ref "U5") (pin "K9") (pinfunction "GND1_K9") (pintype "power_in"))
      (node (ref "U5") (pin "L9") (pinfunction "GND0_L9") (pintype "power_in"))
      (node (ref "X1") (pin "2") (pinfunction "GND_2") (pintype "power_in"))
    )
    (net (code "59") (name "Net-(FB2-Pad1)") (class "Default")
      (node (ref "FB2") (pin "1") (pinfunction "1_1") (pintype "passive"))
      (node (ref "R65") (pin "2") (pintype "passive"))
    )
    (net (code "60") (name "Net-(LED1-PadK)") (class "Default")
      (node (ref "LED1") (pin "K") (pinfunction "K_K") (pintype "passive"))
      (node (ref "R32") (pin "2") (pintype "passive"))
    )
    (net (code "61") (name "Net-(LED2-PadK)") (class "Default")
      (node (ref "LED2") (pin "K") (pinfunction "K_K") (pintype "passive"))
      (node (ref "R31") (pin "2") (pintype "passive"))
    )
    (net (code "62") (name "Net-(LED3-PadK)") (class "Default")
      (node (ref "LED3") (pin "K") (pinfunction "K_K") (pintype "passive"))
      (node (ref "R30") (pin "2") (pintype "passive"))
    )
    (net (code "63") (name "Net-(LED4-PadK)") (class "Default")
      (node (ref "LED4") (pin "K") (pinfunction "K_K") (pintype "passive"))
      (node (ref "R29") (pin "2") (pintype "passive"))
    )
    (net (code "64") (name "Net-(Q6-B)") (class "Default")
      (node (ref "Q6") (pin "1") (pinfunction "B_1") (pintype "passive"))
      (node (ref "R27") (pin "1") (pintype "passive"))
    )
    (net (code "65") (name "Net-(Q6-C)") (class "Default")
      (node (ref "Q6") (pin "3") (pinfunction "C_3") (pintype "passive"))
      (node (ref "R25") (pin "2") (pintype "passive"))
    )
    (net (code "66") (name "Net-(U5B-MFCIO01)") (class "Default")
      (node (ref "R63") (pin "1") (pintype "passive"))
      (node (ref "U5") (pin "J9") (pinfunction "MFCIO01_J9") (pintype "bidirectional"))
    )
    (net (code "67") (name "Net-(U5B-MFCIO02)") (class "Default")
      (node (ref "R64") (pin "1") (pintype "passive"))
      (node (ref "U5") (pin "J10") (pinfunction "MFCIO02_J10") (pintype "bidirectional"))
    )
    (net (code "68") (name "unconnected-(U5A-CLK16_OUT-PadH7)") (class "Default")
      (node (ref "U5") (pin "H7") (pinfunction "CLK16_OUT_H7") (pintype "output+no_connect"))
    )
    (net (code "69") (name "unconnected-(U5A-CLKO_100-PadL6)") (class "Default")
      (node (ref "U5") (pin "L6") (pinfunction "CLKO_100_L6") (pintype "output+no_connect"))
    )
    (net (code "70") (name "unconnected-(U5A-MFC_CTRL_SPI_MISO-PadE7)") (class "Default")
      (node (ref "U5") (pin "E7") (pinfunction "MFC_CTRL_SPI_MISO_E7") (pintype "output+no_connect"))
    )
    (net (code "71") (name "unconnected-(U5A-MFC_CTRL_SPI_MOSI-PadC4)") (class "Default")
      (node (ref "U5") (pin "C4") (pinfunction "MFC_CTRL_SPI_MOSI_C4") (pintype "input+no_connect"))
    )
    (net (code "72") (name "unconnected-(U5A-MFC_CTRL_SPI_SCK-PadE4)") (class "Default")
      (node (ref "U5") (pin "E4") (pinfunction "MFC_CTRL_SPI_SCK_E4") (pintype "input+no_connect"))
    )
    (net (code "73") (name "unconnected-(U5A-MFC_HV0(MFCIO16)-PadA4)") (class "Default")
      (node (ref "U5") (pin "A4") (pinfunction "MFC_HV0(MFCIO16)_A4") (pintype "bidirectional+no_connect"))
    )
    (net (code "74") (name "unconnected-(U5A-MFC_HV1(MFCIO17)-PadA5)") (class "Default")
      (node (ref "U5") (pin "A5") (pinfunction "MFC_HV1(MFCIO17)_A5") (pintype "bidirectional+no_connect"))
    )
    (net (code "75") (name "unconnected-(U5A-MFC_HV2(MFCIO18)-PadA6)") (class "Default")
      (node (ref "U5") (pin "A6") (pinfunction "MFC_HV2(MFCIO18)_A6") (pintype "bidirectional+no_connect"))
    )
    (net (code "76") (name "unconnected-(U5A-MFC_HV3(MFCIO19)-PadA7)") (class "Default")
      (node (ref "U5") (pin "A7") (pinfunction "MFC_HV3(MFCIO19)_A7") (pintype "bidirectional+no_connect"))
    )
    (net (code "77") (name "unconnected-(U5A-MFC_HV4(MFCIO20)-PadA8)") (class "Default")
      (node (ref "U5") (pin "A8") (pinfunction "MFC_HV4(MFCIO20)_A8") (pintype "bidirectional+no_connect"))
    )
    (net (code "78") (name "unconnected-(U5A-MFC_HV5(MFCIO21)-PadA9)") (class "Default")
      (node (ref "U5") (pin "A9") (pinfunction "MFC_HV5(MFCIO21)_A9") (pintype "bidirectional+no_connect"))
    )
    (net (code "79") (name "unconnected-(U5A-MFC_HV6(MFCIO22)-PadA10)") (class "Default")
      (node (ref "U5") (pin "A10") (pinfunction "MFC_HV6(MFCIO22)_A10") (pintype "bidirectional+no_connect"))
    )
    (net (code "80") (name "unconnected-(U5A-MFC_HV7(MFCIO23)-PadA11)") (class "Default")
      (node (ref "U5") (pin "A11") (pinfunction "MFC_HV7(MFCIO23)_A11") (pintype "bidirectional+no_connect"))
    )
    (net (code "81") (name "unconnected-(U5A-RXDV0-PadB2)") (class "Default")
      (node (ref "U5") (pin "B2") (pinfunction "RXDV0_B2") (pintype "input+no_connect"))
    )
    (net (code "82") (name "unconnected-(U5A-RXDV1-PadK2)") (class "Default")
      (node (ref "U5") (pin "K2") (pinfunction "RXDV1_K2") (pintype "input+no_connect"))
    )
    (net (code "83") (name "unconnected-(U5A-SW0-PadL8)") (class "Default")
      (node (ref "U5") (pin "L8") (pinfunction "SW0_L8") (pintype "output+no_connect"))
    )
    (net (code "84") (name "unconnected-(U5A-SW1-PadL10)") (class "Default")
      (node (ref "U5") (pin "L10") (pinfunction "SW1_L10") (pintype "output+no_connect"))
    )
    (net (code "85") (name "unconnected-(U5A-SW_DIODE-PadK7)") (class "Default")
      (node (ref "U5") (pin "K7") (pinfunction "SW_DIODE_K7") (pintype "input+no_connect"))
    )
    (net (code "86") (name "unconnected-(U5A-TST_ANA-PadD5)") (class "Default")
      (node (ref "U5") (pin "D5") (pinfunction "TST_ANA_D5") (pintype "output+no_connect"))
    )
    (net (code "87") (name "unconnected-(U5A-TXER0-PadC2)") (class "Default")
      (node (ref "U5") (pin "C2") (pinfunction "TXER0_C2") (pintype "input+no_connect"))
    )
    (net (code "88") (name "unconnected-(U5A-TXER1-PadJ2)") (class "Default")
      (node (ref "U5") (pin "J2") (pinfunction "TXER1_J2") (pintype "input+no_connect"))
    )
    (net (code "89") (name "unconnected-(U5A-VOUT-PadK10)") (class "Default")
      (node (ref "U5") (pin "K10") (pinfunction "VOUT_K10") (pintype "power_in+no_connect"))
    )
    (net (code "90") (name "unconnected-(U5A-VOUT_FB-PadK11)") (class "Default")
      (node (ref "U5") (pin "K11") (pinfunction "VOUT_FB_K11") (pintype "input+no_connect"))
    )
    (net (code "91") (name "unconnected-(U5B-MFCIO04-PadH8)") (class "Default")
      (node (ref "U5") (pin "H8") (pinfunction "MFCIO04_H8") (pintype "bidirectional+no_connect"))
    )
    (net (code "92") (name "unconnected-(U5B-MFCIO05-PadH9)") (class "Default")
      (node (ref "U5") (pin "H9") (pinfunction "MFCIO05_H9") (pintype "bidirectional+no_connect"))
    )
    (net (code "93") (name "unconnected-(U5B-MFCIO06-PadH10)") (class "Default")
      (node (ref "U5") (pin "H10") (pinfunction "MFCIO06_H10") (pintype "bidirectional+no_connect"))
    )
    (net (code "94") (name "unconnected-(U5B-MFCIO07-PadH11)") (class "Default")
      (node (ref "U5") (pin "H11") (pinfunction "MFCIO07_H11") (pintype "bidirectional+no_connect"))
    )
    (net (code "95") (name "unconnected-(U5B-MFCIO08-PadD8)") (class "Default")
      (node (ref "U5") (pin "D8") (pinfunction "MFCIO08_D8") (pintype "bidirectional+no_connect"))
    )
    (net (code "96") (name "unconnected-(U5B-MFCIO09-PadD9)") (class "Default")
      (node (ref "U5") (pin "D9") (pinfunction "MFCIO09_D9") (pintype "bidirectional+no_connect"))
    )
    (net (code "97") (name "unconnected-(U5B-MFCIO10-PadD10)") (class "Default")
      (node (ref "U5") (pin "D10") (pinfunction "MFCIO10_D10") (pintype "bidirectional+no_connect"))
    )
    (net (code "98") (name "unconnected-(U5B-MFCIO11-PadD11)") (class "Default")
      (node (ref "U5") (pin "D11") (pinfunction "MFCIO11_D11") (pintype "bidirectional+no_connect"))
    )
    (net (code "99") (name "unconnected-(U5B-MFCIO12-PadC8)") (class "Default")
      (node (ref "U5") (pin "C8") (pinfunction "MFCIO12_C8") (pintype "bidirectional+no_connect"))
    )
    (net (code "100") (name "unconnected-(U5B-MFCIO13-PadC9)") (class "Default")
      (node (ref "U5") (pin "C9") (pinfunction "MFCIO13_C9") (pintype "bidirectional+no_connect"))
    )
    (net (code "101") (name "unconnected-(U5B-MFCIO14-PadC10)") (class "Default")
      (node (ref "U5") (pin "C10") (pinfunction "MFCIO14_C10") (pintype "bidirectional+no_connect"))
    )
    (net (code "102") (name "unconnected-(U5B-MFCIO15-PadC11)") (class "Default")
      (node (ref "U5") (pin "C11") (pinfunction "MFCIO15_C11") (pintype "bidirectional+no_connect"))
    )
    (net (code "103") (name "unconnected-(U5B-RXCLK0-PadD2)") (class "Default")
      (node (ref "U5") (pin "D2") (pinfunction "RXCLK0_D2") (pintype "bidirectional+no_connect"))
    )
    (net (code "104") (name "unconnected-(U5B-RXCLK1-PadG2)") (class "Default")
      (node (ref "U5") (pin "G2") (pinfunction "RXCLK1_G2") (pintype "bidirectional+no_connect"))
    )
    (net (code "105") (name "unconnected-(U5B-TXCLK0-PadE2)") (class "Default")
      (node (ref "U5") (pin "E2") (pinfunction "TXCLK0_E2") (pintype "bidirectional+no_connect"))
    )
    (net (code "106") (name "unconnected-(U5B-TXCLK1-PadH2)") (class "Default")
      (node (ref "U5") (pin "H2") (pinfunction "TXCLK1_H2") (pintype "bidirectional+no_connect"))
    )
    (net (code "107") (name "unconnected-(U5B-VIO1-PadB5)") (class "Default")
      (node (ref "U5") (pin "B5") (pinfunction "VIO1_B5") (pintype "power_in+no_connect"))
    )
    (net (code "108") (name "unconnected-(U5B-VIO2-PadB7)") (class "Default")
      (node (ref "U5") (pin "B7") (pinfunction "VIO2_B7") (pintype "power_in+no_connect"))
    )
    (net (code "109") (name "unconnected-(U5B-VIO3-PadB9)") (class "Default")
      (node (ref "U5") (pin "B9") (pinfunction "VIO3_B9") (pintype "power_in+no_connect"))
    )
    (net (code "110") (name "unconnected-(U5B-VS0-PadL7)") (class "Default")
      (node (ref "U5") (pin "L7") (pinfunction "VS0_L7") (pintype "power_in+no_connect"))
    )
    (net (code "111") (name "unconnected-(U5B-VS1-PadL11)") (class "Default")
      (node (ref "U5") (pin "L11") (pinfunction "VS1_L11") (pintype "input+no_connect"))
    )
    (net (code "112") (name "unconnected-(X1-OE{slash}~{ST}{slash}NC-Pad1)") (class "Default")
      (node (ref "X1") (pin "1") (pinfunction "OE/~{ST}/NC_1") (pintype "passive"))
    )
  )
)
